# Gero_Board.net
KiCad netlist of a schematic drawn in Altium Designer
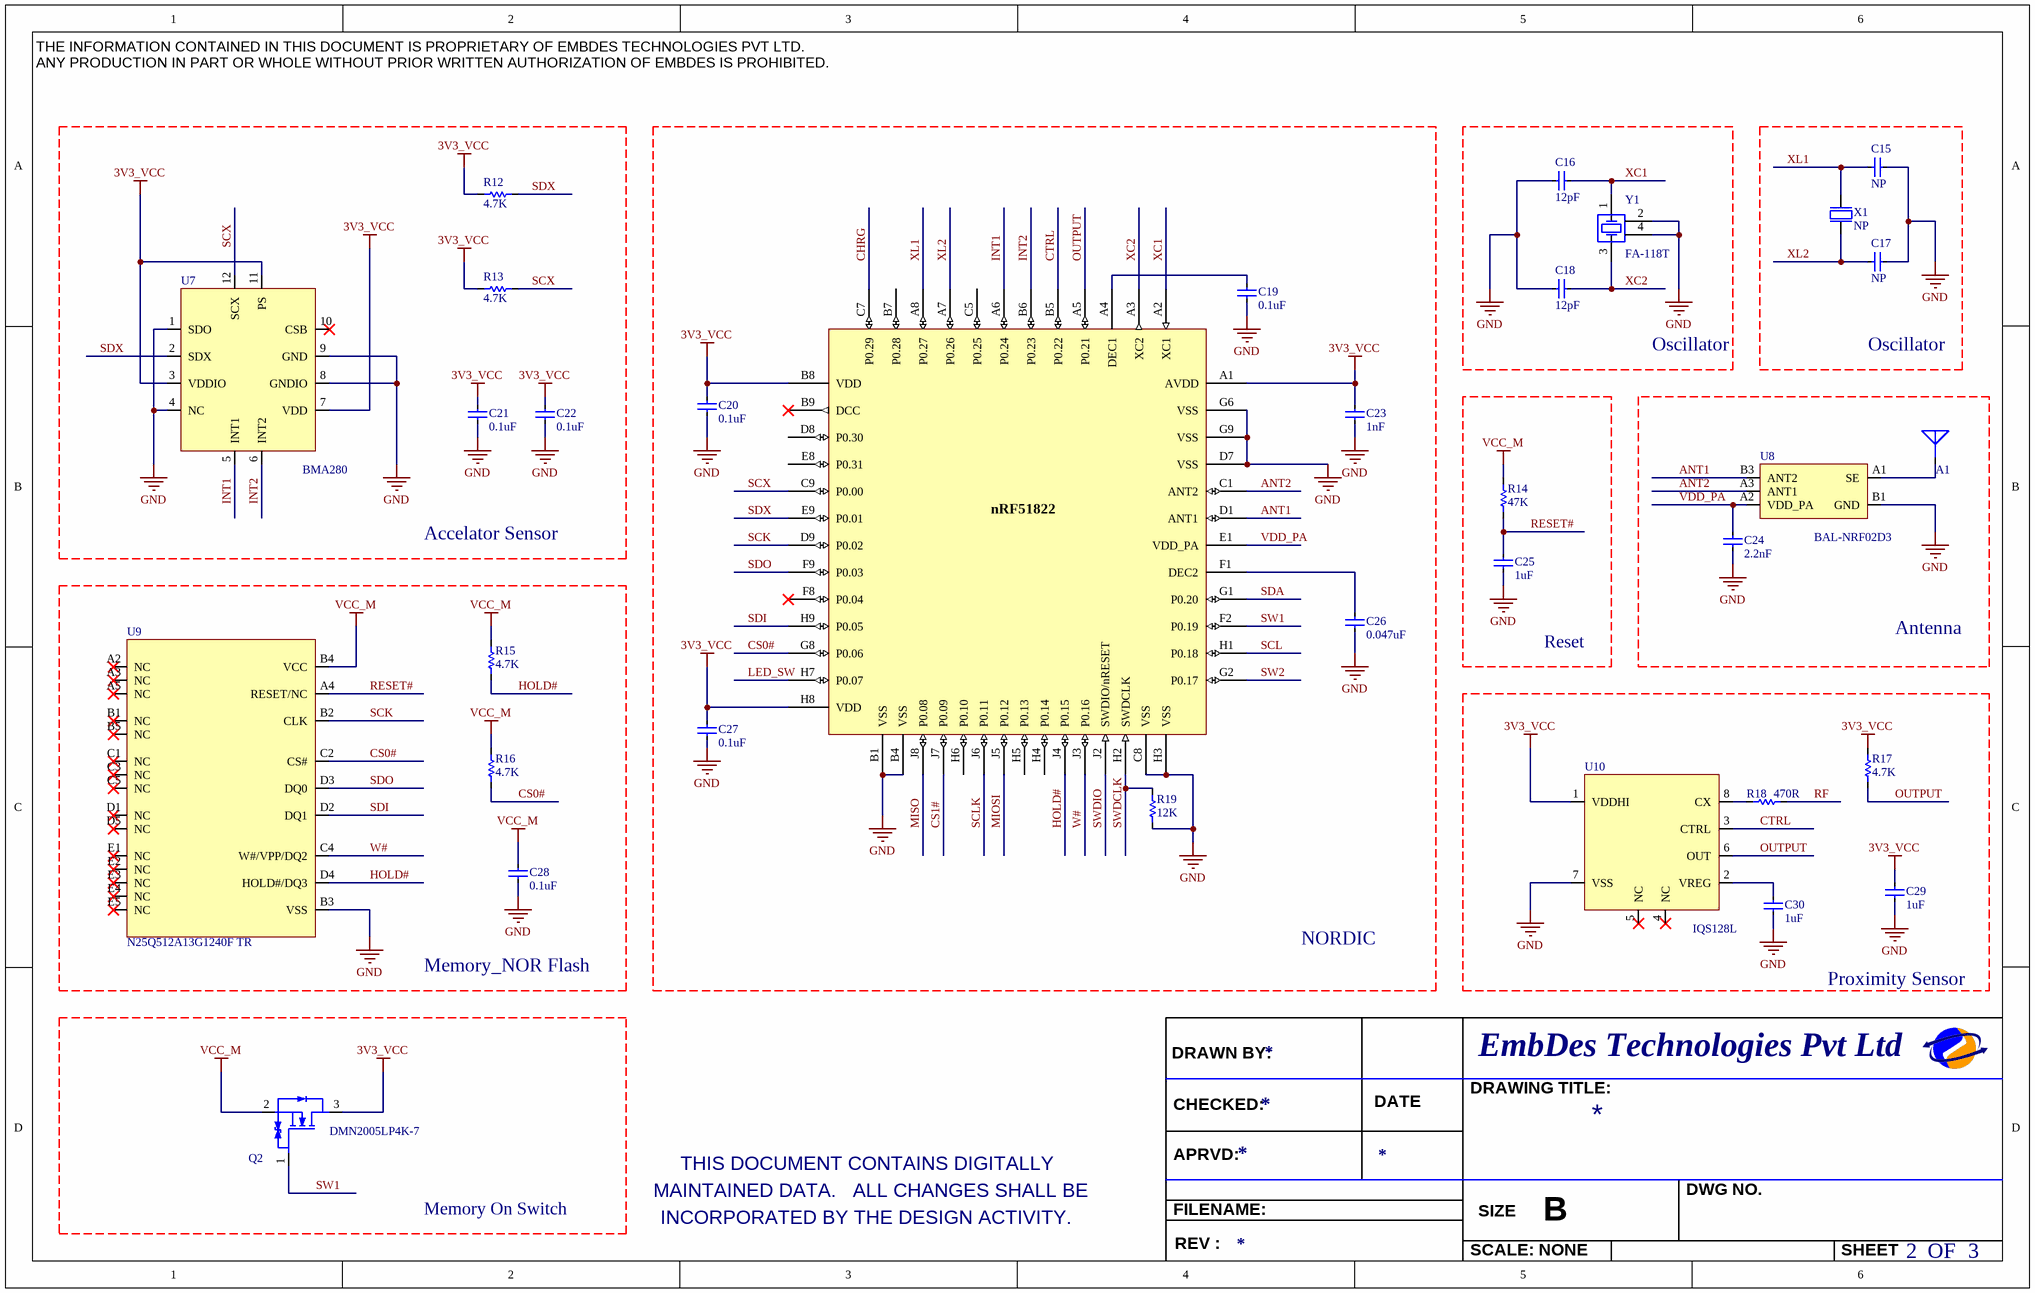
[diagram p0: Gero_Board..SchDoc]

(export (version "E")
  (design (tool "Eeschema 10.0.6"))
  (components
    (comp (ref "*1")
      (value "ol Bluetooth Low Energy and 2.4GHz proprietary system-on-chip")
      (libsource (lib "Gero_Board") (part "ol Bluetooth Low Energy and 2.4GHz proprietary system-on-chip"))
    )
    (comp (ref "A1")
      (value "DCAK0008-Dielectric Chip Antenna")
      (fields
        (field (name "MANUFACTURER") "CIROCOMM TECHNOLOGY")
        (field (name "MANUFACUTURER PART NO") "03A40D5M00J0110")
      )
      (libsource (lib "Gero_Board") (part "DCAK0008-Dielectric Chip Antenna"))
    )
    (comp (ref "C15")
      (value "NP")
      (footprint "CAPC1005X04L")
      (description "CAP CER 12PF 25V 5% NP0 0201")
      (fields
        (field (name "MANUFACTURER") "TDK Corporation")
        (field (name "MANUFACTURER PART NUMBER") "C0603C0G1E120J030BA")
      )
      (libsource (lib "Gero_Board") (part "CAP CER 12PF 25V 5% NP0 0201"))
    )
    (comp (ref "C16")
      (value "12pF")
      (footprint "CAPC1005X04L")
      (description "CAP CER 12PF 25V 5% NP0 0201")
      (fields
        (field (name "MANUFACTURER") "TDK Corporation")
        (field (name "MANUFACTURER PART NUMBER") "C0603C0G1E120J030BA")
      )
      (libsource (lib "Gero_Board") (part "CAP CER 12PF 25V 5% NP0 0201"))
    )
    (comp (ref "C17")
      (value "NP")
      (footprint "CAPC1005X04L")
      (description "CAP CER 12PF 25V 5% NP0 0201")
      (fields
        (field (name "MANUFACTURER") "TDK Corporation")
        (field (name "MANUFACTURER PART NUMBER") "C0603C0G1E120J030BA")
      )
      (libsource (lib "Gero_Board") (part "CAP CER 12PF 25V 5% NP0 0201"))
    )
    (comp (ref "C18")
      (value "12pF")
      (footprint "CAPC1005X04L")
      (description "CAP CER 12PF 25V 5% NP0 0201")
      (fields
        (field (name "MANUFACTURER") "TDK Corporation")
        (field (name "MANUFACTURER PART NUMBER") "C0603C0G1E120J030BA")
      )
      (libsource (lib "Gero_Board") (part "CAP CER 12PF 25V 5% NP0 0201"))
    )
    (comp (ref "C19")
      (value "0.1uF")
      (footprint "CAPC1005X04L")
      (description "CAP CER 0.1UF 16V 10% X5R 0201")
      (fields
        (field (name "MANUFACTURER") "TDK Corporation")
        (field (name "MANUFACTURER PART NUMBER") "C0603X5R1C104K030BC")
      )
      (libsource (lib "Gero_Board") (part "CAP CER 0.1UF 16V 10% X5R 0201"))
    )
    (comp (ref "C20")
      (value "0.1uF")
      (footprint "CAPC1005X04L")
      (description "CAP CER 0.1UF 16V 10% X5R 0201")
      (fields
        (field (name "MANUFACTURER") "TDK Corporation")
        (field (name "MANUFACTURER PART NUMBER") "C0603X5R1C104K030BC")
      )
      (libsource (lib "Gero_Board") (part "CAP CER 0.1UF 16V 10% X5R 0201"))
    )
    (comp (ref "C21")
      (value "0.1uF")
      (footprint "CAPC1005X04L")
      (description "CAP CER 0.1UF 16V 10% X5R 0201")
      (fields
        (field (name "MANUFACTURER") "TDK Corporation")
        (field (name "MANUFACTURER PART NUMBER") "C0603X5R1C104K030BC")
      )
      (libsource (lib "Gero_Board") (part "CAP CER 0.1UF 16V 10% X5R 0201"))
    )
    (comp (ref "C22")
      (value "0.1uF")
      (footprint "CAPC1005X04L")
      (description "CAP CER 0.1UF 16V 10% X5R 0201")
      (fields
        (field (name "MANUFACTURER") "TDK Corporation")
        (field (name "MANUFACTURER PART NUMBER") "C0603X5R1C104K030BC")
      )
      (libsource (lib "Gero_Board") (part "CAP CER 0.1UF 16V 10% X5R 0201"))
    )
    (comp (ref "C23")
      (value "1nF")
      (footprint "CAPC1005X04L")
      (description "CAP CER 1000PF 25V 10% X7R 0201")
      (fields
        (field (name "MANUFACTURER") "TDK Corporation")
        (field (name "MANUFACTURER PART NUMBER") "C0603X7R1E102K030BA")
      )
      (libsource (lib "Gero_Board") (part "CAP CER 1000PF 25V 10% X7R 0201"))
    )
    (comp (ref "C24")
      (value "2.2nF")
      (footprint "CAPC1005X04L")
      (description "CAP CER 2200PF 16V 10% X7R 0201")
      (fields
        (field (name "MANUFACTURER") "TDK Corporation")
        (field (name "MANUFACTURER PART NUMBER") "C0603X7R1C222K030BA")
      )
      (libsource (lib "Gero_Board") (part "CAP CER 2200PF 16V 10% X7R 0201"))
    )
    (comp (ref "C25")
      (value "1uF")
      (footprint "CAPC1005X04L")
      (description "CAP CER 1UF 16V 10% X5R 0402")
      (fields
        (field (name "MANUFACTURER") "TDK Corporation")
        (field (name "MANUFACTURER PART NUMBER") "C1005X5R1C105K050BC")
      )
      (libsource (lib "Gero_Board.~(283)") (part "CAP CER 1UF 16V 10% X5R 0402"))
    )
    (comp (ref "C26")
      (value "0.047uF")
      (footprint "CAPC1005X04L")
      (description "CAP CER 0.047UF 16V 10% X6S 0201")
      (fields
        (field (name "MANUFACTURER") "TDK Corporation")
        (field (name "MANUFACTURER PART NUMBER") "C0603X6S1C473K030BC")
      )
      (libsource (lib "Gero_Board") (part "CAP CER 0.047UF 16V 10% X6S 0201"))
    )
    (comp (ref "C27")
      (value "0.1uF")
      (footprint "CAPC1005X04L")
      (description "CAP CER 0.1UF 16V 10% X5R 0201")
      (fields
        (field (name "MANUFACTURER") "TDK Corporation")
        (field (name "MANUFACTURER PART NUMBER") "C0603X5R1C104K030BC")
      )
      (libsource (lib "Gero_Board") (part "CAP CER 0.1UF 16V 10% X5R 0201"))
    )
    (comp (ref "C28")
      (value "0.1uF")
      (footprint "CAPC1005X04L")
      (description "CAP CER 0.1UF 16V 10% X5R 0201")
      (fields
        (field (name "MANUFACTURER") "TDK Corporation")
        (field (name "MANUFACTURER PART NUMBER") "C0603X5R1C104K030BC")
      )
      (libsource (lib "Gero_Board") (part "CAP CER 0.1UF 16V 10% X5R 0201"))
    )
    (comp (ref "C29")
      (value "1uF")
      (footprint "CAPC1005X04L")
      (description "CAP CER 1UF 16V 10% X5R 0402")
      (fields
        (field (name "MANUFACTURER") "TDK Corporation")
        (field (name "MANUFACTURER PART NUMBER") "C1005X5R1C105K050BC")
      )
      (libsource (lib "Gero_Board.~(283)") (part "CAP CER 1UF 16V 10% X5R 0402"))
    )
    (comp (ref "C30")
      (value "1uF")
      (footprint "CAPC1005X04L")
      (description "CAP CER 1UF 16V 10% X5R 0402")
      (fields
        (field (name "MANUFACTURER") "TDK Corporation")
        (field (name "MANUFACTURER PART NUMBER") "C1005X5R1C105K050BC")
      )
      (libsource (lib "Gero_Board.~(283)") (part "CAP CER 1UF 16V 10% X5R 0402"))
    )
    (comp (ref "Q2")
      (value "MOSFET N-CH 20V 200MA 3-DFN")
      (fields (field (name "MANUFACTURER") "Diodes Inc") (field (name "MFG PART NO") "DMN2005LP4K-7"))
      (libsource (lib "Gero_Board.~(283)") (part "MOSFET N-CH 20V 200MA 3-DFN"))
    )
    (comp (ref "R12")
      (value "4.7K")
      (footprint "R0402")
      (description "RES 4.7K OHM 1/20W 1% 0201 SMD")
      (fields (field (name "MANUFACTURER") "Panasonic Electronic Components"))
      (libsource (lib "Gero_Board") (part "RES 4.7K OHM 1/20W 1% 0201 SMD"))
    )
    (comp (ref "R13")
      (value "4.7K")
      (footprint "R0402")
      (description "RES 4.7K OHM 1/20W 1% 0201 SMD")
      (fields (field (name "MANUFACTURER") "Panasonic Electronic Components"))
      (libsource (lib "Gero_Board") (part "RES 4.7K OHM 1/20W 1% 0201 SMD"))
    )
    (comp (ref "R14")
      (value "47K")
      (footprint "R0402")
      (description "RES 47K OHM 1/20W 1% 0201 SMD")
      (fields (field (name "MANUFACTURER") "Panasonic Electronic Components"))
      (libsource (lib "Gero_Board") (part "RES 47K OHM 1/20W 1% 0201 SMD"))
    )
    (comp (ref "R15")
      (value "4.7K")
      (footprint "R0402")
      (description "RES 4.7K OHM 1/20W 1% 0201 SMD")
      (fields (field (name "MANUFACTURER") "Panasonic Electronic Components"))
      (libsource (lib "Gero_Board") (part "RES 4.7K OHM 1/20W 1% 0201 SMD"))
    )
    (comp (ref "R16")
      (value "4.7K")
      (footprint "R0402")
      (description "RES 4.7K OHM 1/20W 1% 0201 SMD")
      (fields (field (name "MANUFACTURER") "Panasonic Electronic Components"))
      (libsource (lib "Gero_Board") (part "RES 4.7K OHM 1/20W 1% 0201 SMD"))
    )
    (comp (ref "R17")
      (value "4.7K")
      (footprint "R0402")
      (description "RES 4.7K OHM 1/20W 1% 0201 SMD")
      (fields (field (name "MANUFACTURER") "Panasonic Electronic Components"))
      (libsource (lib "Gero_Board") (part "RES 4.7K OHM 1/20W 1% 0201 SMD"))
    )
    (comp (ref "R18")
      (value "470R")
      (footprint "R0402")
      (description "RES 470 OHM 1/20W 1% 0201 SMD")
      (fields (field (name "MANUFACTURER") "Panasonic Electronic Components"))
      (libsource (lib "Gero_Board") (part "RES 470 OHM 1/20W 1% 0201 SMD"))
    )
    (comp (ref "R19")
      (value "12K")
      (footprint "R0402")
      (description "RES 12K OHM 1/20W 1% 0201 SMD")
      (libsource (lib "Gero_Board") (part "RES 12K OHM 1/20W 1% 0201 SMD"))
    )
    (comp (ref "U7")
      (value "SENSOR ACCELEROMETER")
      (fields
        (field (name "MANUFACTURER") "Bosch Sensortec")
        (field (name "MANUFACTURER PART NUMBER") "BMA280")
      )
      (libsource (lib "Gero_Board.~(283)") (part "SENSOR ACCELEROMETER"))
    )
    (comp (ref "U8")
      (value "50 ohm balun transformer for 2.45GHz ISM")
      (footprint "BAL-NRF02D3")
      (fields
        (field (name "MANUFACTURER") "ST Microelectronics")
        (field (name "MANUFACTURER PART NUMBER") "BAL-NRF02D3")
      )
      (libsource (lib "Gero_Board.~(283)") (part "50 ohm balun transformer for 2.45GHz ISM"))
    )
    (comp (ref "U9")
      (value "IC FLASH 128MX4 SLC TBGA DDP")
      (footprint "N25Q512A13G1240F")
      (fields
        (field (name "MANUFACTURER") "Micron Technology Inc")
        (field (name "MANUFACTURER PART NUMBER") "N25Q512A13G1240F TR")
      )
      (libsource (lib "Gero_Board.~(283)") (part "IC FLASH 128MX4 SLC TBGA DDP"))
    )
    (comp (ref "U10")
      (value "Single Channel Capacitive Proximity/Touch Controller")
      (footprint "IQS128")
      (fields (field (name "MANUFACTURER") "Azoteq") (field (name "MANUFACTURER PART NO") "IQS128L"))
      (libsource (lib "Gero_Board.~(283)") (part "Single Channel Capacitive Proximity/Touch Controller"))
    )
    (comp (ref "X1")
      (value "NP")
      (fields (field (name "Comment") "xtal"))
      (libsource (lib "Gero_Board") (part "xtal"))
    )
    (comp (ref "Y1")
      (value "MHz Range Crystal Unit Ultra Miniature Size Low Profile SMD")
      (footprint "FA-118T")
      (fields (field (name "MANUFACTURER") "EPSON") (field (name "MANUFACTURER PART NUMBER") "FA-118T"))
      (libsource (lib "Gero_Board.~(283)") (part "MHz Range Crystal Unit Ultra Miniature Size Low Profile SMD"))
    )
  )
  (nets
    (net (code "1") (name "/ANT1") (class "Default")
      (node (ref "*1") (pin "D1") (pinfunction "ANT1_D1") (pintype "bidirectional"))
      (node (ref "U8") (pin "B3") (pinfunction "ANT2_B3") (pintype "passive"))
    )
    (net (code "2") (name "/ANT2") (class "Default")
      (node (ref "*1") (pin "C1") (pinfunction "ANT2_C1") (pintype "bidirectional"))
      (node (ref "U8") (pin "A3") (pinfunction "ANT1_A3") (pintype "passive"))
    )
    (net (code "3") (name "/CHRG") (class "Default")
      (node (ref "*1") (pin "C7") (pinfunction "P0.29_C7") (pintype "bidirectional"))
    )
    (net (code "4") (name "/CS0#") (class "Default")
      (node (ref "*1") (pin "G8") (pinfunction "P0.06_G8") (pintype "bidirectional"))
      (node (ref "R16") (pin "1") (pinfunction "1_1") (pintype "passive"))
      (node (ref "U9") (pin "C2") (pinfunction "CS#_C2") (pintype "passive"))
    )
    (net (code "5") (name "/CS1#") (class "Default")
      (node (ref "*1") (pin "J7") (pinfunction "P0.09_J7") (pintype "bidirectional"))
    )
    (net (code "6") (name "/CTRL") (class "Default")
      (node (ref "*1") (pin "B5") (pinfunction "P0.22_B5") (pintype "bidirectional"))
      (node (ref "U10") (pin "3") (pinfunction "CTRL_3") (pintype "passive"))
    )
    (net (code "7") (name "/HOLD#") (class "Default")
      (node (ref "*1") (pin "J4") (pinfunction "P0.15_J4") (pintype "bidirectional"))
      (node (ref "R15") (pin "1") (pinfunction "1_1") (pintype "passive"))
      (node (ref "U9") (pin "D4") (pinfunction "HOLD#/DQ3_D4") (pintype "passive"))
    )
    (net (code "8") (name "/INT1") (class "Default")
      (node (ref "*1") (pin "A6") (pinfunction "P0.24_A6") (pintype "bidirectional"))
      (node (ref "U7") (pin "5") (pinfunction "INT1_5") (pintype "passive"))
    )
    (net (code "9") (name "/INT2") (class "Default")
      (node (ref "*1") (pin "B6") (pinfunction "P0.23_B6") (pintype "bidirectional"))
      (node (ref "U7") (pin "6") (pinfunction "INT2_6") (pintype "passive"))
    )
    (net (code "10") (name "/LED_SW") (class "Default")
      (node (ref "*1") (pin "H7") (pinfunction "P0.07_H7") (pintype "bidirectional"))
    )
    (net (code "11") (name "/MIOSI") (class "Default")
      (node (ref "*1") (pin "J5") (pinfunction "P0.12_J5") (pintype "bidirectional"))
    )
    (net (code "12") (name "/MISO") (class "Default")
      (node (ref "*1") (pin "J8") (pinfunction "P0.08_J8") (pintype "bidirectional"))
    )
    (net (code "13") (name "/OUTPUT") (class "Default")
      (node (ref "*1") (pin "A5") (pinfunction "P0.21_A5") (pintype "bidirectional"))
      (node (ref "R17") (pin "1") (pinfunction "1_1") (pintype "passive"))
      (node (ref "U10") (pin "6") (pinfunction "OUT_6") (pintype "passive"))
    )
    (net (code "14") (name "/RESET#") (class "Default")
      (node (ref "C25") (pin "2") (pinfunction "2_2") (pintype "passive"))
      (node (ref "R14") (pin "1") (pinfunction "1_1") (pintype "passive"))
      (node (ref "U9") (pin "A4") (pinfunction "RESET/NC_A4") (pintype "passive"))
    )
    (net (code "15") (name "/RF") (class "Default")
      (node (ref "R18") (pin "2") (pinfunction "2_2") (pintype "passive"))
    )
    (net (code "16") (name "/SCK") (class "Default")
      (node (ref "*1") (pin "D9") (pinfunction "P0.02_D9") (pintype "bidirectional"))
      (node (ref "U9") (pin "B2") (pinfunction "CLK_B2") (pintype "passive"))
    )
    (net (code "17") (name "/SCL") (class "Default")
      (node (ref "*1") (pin "H1") (pinfunction "P0.18_H1") (pintype "bidirectional"))
    )
    (net (code "18") (name "/SCLK") (class "Default")
      (node (ref "*1") (pin "J6") (pinfunction "P0.11_J6") (pintype "bidirectional"))
    )
    (net (code "19") (name "/SCX") (class "Default")
      (node (ref "*1") (pin "C9") (pinfunction "P0.00_C9") (pintype "bidirectional"))
      (node (ref "R13") (pin "2") (pinfunction "2_2") (pintype "passive"))
      (node (ref "U7") (pin "12") (pinfunction "SCX_12") (pintype "passive"))
    )
    (net (code "20") (name "/SDA") (class "Default")
      (node (ref "*1") (pin "G1") (pinfunction "P0.20_G1") (pintype "bidirectional"))
    )
    (net (code "21") (name "/SDI") (class "Default")
      (node (ref "*1") (pin "H9") (pinfunction "P0.05_H9") (pintype "bidirectional"))
      (node (ref "U9") (pin "D2") (pinfunction "DQ1_D2") (pintype "passive"))
    )
    (net (code "22") (name "/SDO") (class "Default")
      (node (ref "*1") (pin "F9") (pinfunction "P0.03_F9") (pintype "bidirectional"))
      (node (ref "U9") (pin "D3") (pinfunction "DQ0_D3") (pintype "passive"))
    )
    (net (code "23") (name "/SDX") (class "Default")
      (node (ref "*1") (pin "E9") (pinfunction "P0.01_E9") (pintype "bidirectional"))
      (node (ref "R12") (pin "2") (pinfunction "2_2") (pintype "passive"))
      (node (ref "U7") (pin "2") (pinfunction "SDX_2") (pintype "passive"))
    )
    (net (code "24") (name "/SW1") (class "Default")
      (node (ref "*1") (pin "F2") (pinfunction "P0.19_F2") (pintype "bidirectional"))
      (node (ref "Q2") (pin "1") (pinfunction "G_1") (pintype "passive"))
    )
    (net (code "25") (name "/SW2") (class "Default")
      (node (ref "*1") (pin "G2") (pinfunction "P0.17_G2") (pintype "bidirectional"))
    )
    (net (code "26") (name "/SWDCLK") (class "Default")
      (node (ref "*1") (pin "H2") (pinfunction "SWDCLK_H2") (pintype "input"))
      (node (ref "R19") (pin "2") (pinfunction "2_2") (pintype "passive"))
    )
    (net (code "27") (name "/SWDIO") (class "Default")
      (node (ref "*1") (pin "J2") (pinfunction "SWDIO/nRESET_J2") (pintype "input"))
    )
    (net (code "28") (name "/VDD_PA") (class "Default")
      (node (ref "*1") (pin "E1") (pinfunction "VDD_PA_E1") (pintype "power_in"))
      (node (ref "C24") (pin "2") (pinfunction "2_2") (pintype "passive"))
      (node (ref "U8") (pin "A2") (pinfunction "VDD_PA_A2") (pintype "passive"))
    )
    (net (code "29") (name "/W#") (class "Default")
      (node (ref "*1") (pin "J3") (pinfunction "P0.16_J3") (pintype "bidirectional"))
      (node (ref "U9") (pin "C4") (pinfunction "W#/VPP/DQ2_C4") (pintype "passive"))
    )
    (net (code "30") (name "/XC1") (class "Default")
      (node (ref "*1") (pin "A2") (pinfunction "XC1_A2") (pintype "input"))
      (node (ref "C16") (pin "2") (pinfunction "2_2") (pintype "passive"))
      (node (ref "Y1") (pin "1") (pinfunction "XTAL_IN_1") (pintype "passive"))
    )
    (net (code "31") (name "/XC2") (class "Default")
      (node (ref "*1") (pin "A3") (pinfunction "XC2_A3") (pintype "output"))
      (node (ref "C18") (pin "2") (pinfunction "2_2") (pintype "passive"))
      (node (ref "Y1") (pin "3") (pinfunction "XTAL_OUT_3") (pintype "passive"))
    )
    (net (code "32") (name "/XL1") (class "Default")
      (node (ref "*1") (pin "A8") (pinfunction "P0.27_A8") (pintype "bidirectional"))
      (node (ref "C15") (pin "1") (pinfunction "1_1") (pintype "passive"))
      (node (ref "X1") (pin "1") (pinfunction "inp_1") (pintype "passive"))
    )
    (net (code "33") (name "/XL2") (class "Default")
      (node (ref "*1") (pin "A7") (pinfunction "P0.26_A7") (pintype "bidirectional"))
      (node (ref "C17") (pin "1") (pinfunction "1_1") (pintype "passive"))
      (node (ref "X1") (pin "3") (pinfunction "out_3") (pintype "passive"))
    )
    (net (code "34") (name "3V3_VCC") (class "Default")
      (node (ref "*1") (pin "A1") (pinfunction "AVDD_A1") (pintype "power_in"))
      (node (ref "*1") (pin "B8") (pinfunction "VDD_B8") (pintype "power_in"))
      (node (ref "*1") (pin "H8") (pinfunction "VDD_H8") (pintype "power_in"))
      (node (ref "C20") (pin "2") (pinfunction "2_2") (pintype "passive"))
      (node (ref "C21") (pin "2") (pinfunction "2_2") (pintype "passive"))
      (node (ref "C22") (pin "2") (pinfunction "2_2") (pintype "passive"))
      (node (ref "C23") (pin "2") (pinfunction "2_2") (pintype "passive"))
      (node (ref "C27") (pin "2") (pinfunction "2_2") (pintype "passive"))
      (node (ref "C29") (pin "2") (pinfunction "2_2") (pintype "passive"))
      (node (ref "Q2") (pin "3") (pinfunction "D_3") (pintype "passive"))
      (node (ref "R12") (pin "1") (pinfunction "1_1") (pintype "passive"))
      (node (ref "R13") (pin "1") (pinfunction "1_1") (pintype "passive"))
      (node (ref "R17") (pin "2") (pinfunction "2_2") (pintype "passive"))
      (node (ref "U10") (pin "1") (pinfunction "VDDHI_1") (pintype "passive"))
      (node (ref "U7") (pin "11") (pinfunction "PS_11") (pintype "passive"))
      (node (ref "U7") (pin "3") (pinfunction "VDDIO_3") (pintype "passive"))
      (node (ref "U7") (pin "7") (pinfunction "VDD_7") (pintype "passive"))
    )
    (net (code "35") (name "GND") (class "Default")
      (node (ref "*1") (pin "B1") (pinfunction "VSS_B1") (pintype "power_in"))
      (node (ref "*1") (pin "B4") (pinfunction "VSS_B4") (pintype "power_in"))
      (node (ref "*1") (pin "C8") (pinfunction "VSS_C8") (pintype "power_in"))
      (node (ref "*1") (pin "D7") (pinfunction "VSS_D7") (pintype "power_in"))
      (node (ref "*1") (pin "G6") (pinfunction "VSS_G6") (pintype "power_in"))
      (node (ref "*1") (pin "G9") (pinfunction "VSS_G9") (pintype "power_in"))
      (node (ref "*1") (pin "H3") (pinfunction "VSS_H3") (pintype "power_in"))
      (node (ref "C15") (pin "2") (pinfunction "2_2") (pintype "passive"))
      (node (ref "C16") (pin "1") (pinfunction "1_1") (pintype "passive"))
      (node (ref "C17") (pin "2") (pinfunction "2_2") (pintype "passive"))
      (node (ref "C18") (pin "1") (pinfunction "1_1") (pintype "passive"))
      (node (ref "C19") (pin "1") (pinfunction "1_1") (pintype "passive"))
      (node (ref "C20") (pin "1") (pinfunction "1_1") (pintype "passive"))
      (node (ref "C21") (pin "1") (pinfunction "1_1") (pintype "passive"))
      (node (ref "C22") (pin "1") (pinfunction "1_1") (pintype "passive"))
      (node (ref "C23") (pin "1") (pinfunction "1_1") (pintype "passive"))
      (node (ref "C24") (pin "1") (pinfunction "1_1") (pintype "passive"))
      (node (ref "C25") (pin "1") (pinfunction "1_1") (pintype "passive"))
      (node (ref "C26") (pin "1") (pinfunction "1_1") (pintype "passive"))
      (node (ref "C27") (pin "1") (pinfunction "1_1") (pintype "passive"))
      (node (ref "C28") (pin "1") (pinfunction "1_1") (pintype "passive"))
      (node (ref "C29") (pin "1") (pinfunction "1_1") (pintype "passive"))
      (node (ref "C30") (pin "1") (pinfunction "1_1") (pintype "passive"))
      (node (ref "R19") (pin "1") (pinfunction "1_1") (pintype "passive"))
      (node (ref "U10") (pin "7") (pinfunction "VSS_7") (pintype "passive"))
      (node (ref "U7") (pin "1") (pinfunction "SDO_1") (pintype "passive"))
      (node (ref "U7") (pin "4") (pinfunction "NC_4") (pintype "passive"))
      (node (ref "U7") (pin "8") (pinfunction "GNDIO_8") (pintype "passive"))
      (node (ref "U7") (pin "9") (pinfunction "GND_9") (pintype "passive"))
      (node (ref "U8") (pin "B1") (pinfunction "GND_B1") (pintype "passive"))
      (node (ref "U9") (pin "B3") (pinfunction "VSS_B3") (pintype "passive"))
      (node (ref "Y1") (pin "2") (pinfunction "GND_2") (pintype "passive"))
      (node (ref "Y1") (pin "4") (pinfunction "GND_4") (pintype "passive"))
    )
    (net (code "36") (name "Net-(*1-DEC1)") (class "Default")
      (node (ref "*1") (pin "A4") (pinfunction "DEC1_A4") (pintype "power_in"))
      (node (ref "C19") (pin "2") (pinfunction "2_2") (pintype "passive"))
    )
    (net (code "37") (name "Net-(*1-DEC2)") (class "Default")
      (node (ref "*1") (pin "F1") (pinfunction "DEC2_F1") (pintype "power_in"))
      (node (ref "C26") (pin "2") (pinfunction "2_2") (pintype "passive"))
    )
    (net (code "38") (name "Net-(U10-CX)") (class "Default")
      (node (ref "R18") (pin "1") (pinfunction "1_1") (pintype "passive"))
      (node (ref "U10") (pin "8") (pinfunction "CX_8") (pintype "passive"))
    )
    (net (code "39") (name "Net-(U10-VREG)") (class "Default")
      (node (ref "C30") (pin "2") (pinfunction "2_2") (pintype "passive"))
      (node (ref "U10") (pin "2") (pinfunction "VREG_2") (pintype "passive"))
    )
    (net (code "40") (name "VCC_M") (class "Default")
      (node (ref "C28") (pin "2") (pinfunction "2_2") (pintype "passive"))
      (node (ref "Q2") (pin "2") (pinfunction "S_2") (pintype "passive"))
      (node (ref "R14") (pin "2") (pinfunction "2_2") (pintype "passive"))
      (node (ref "R15") (pin "2") (pinfunction "2_2") (pintype "passive"))
      (node (ref "R16") (pin "2") (pinfunction "2_2") (pintype "passive"))
      (node (ref "U9") (pin "B4") (pinfunction "VCC_B4") (pintype "passive"))
    )
    (net (code "41") (name "unconnected-(*1-DCC-PadB9)") (class "Default")
      (node (ref "*1") (pin "B9") (pinfunction "DCC_B9") (pintype "output+no_connect"))
    )
    (net (code "42") (name "unconnected-(*1-P0.04-PadF8)") (class "Default")
      (node (ref "*1") (pin "F8") (pinfunction "P0.04_F8") (pintype "bidirectional+no_connect"))
    )
    (net (code "43") (name "unconnected-(*1-P0.10-PadH6)") (class "Default")
      (node (ref "*1") (pin "H6") (pinfunction "P0.10_H6") (pintype "bidirectional"))
    )
    (net (code "44") (name "unconnected-(*1-P0.13-PadH5)") (class "Default")
      (node (ref "*1") (pin "H5") (pinfunction "P0.13_H5") (pintype "bidirectional"))
    )
    (net (code "45") (name "unconnected-(*1-P0.14-PadH4)") (class "Default")
      (node (ref "*1") (pin "H4") (pinfunction "P0.14_H4") (pintype "bidirectional"))
    )
    (net (code "46") (name "unconnected-(*1-P0.25-PadC5)") (class "Default")
      (node (ref "*1") (pin "C5") (pinfunction "P0.25_C5") (pintype "bidirectional"))
    )
    (net (code "47") (name "unconnected-(*1-P0.28-PadB7)") (class "Default")
      (node (ref "*1") (pin "B7") (pinfunction "P0.28_B7") (pintype "bidirectional"))
    )
    (net (code "48") (name "unconnected-(*1-P0.30-PadD8)") (class "Default")
      (node (ref "*1") (pin "D8") (pinfunction "P0.30_D8") (pintype "bidirectional"))
    )
    (net (code "49") (name "unconnected-(*1-P0.31-PadE8)") (class "Default")
      (node (ref "*1") (pin "E8") (pinfunction "P0.31_E8") (pintype "bidirectional"))
    )
    (net (code "50") (name "unconnected-(A1-A-Pad1)") (class "Default")
      (node (ref "A1") (pin "1") (pinfunction "A_1") (pintype "passive"))
    )
    (net (code "51") (name "unconnected-(U7-CSB-Pad10)") (class "Default")
      (node (ref "U7") (pin "10") (pinfunction "CSB_10") (pintype "passive+no_connect"))
    )
    (net (code "52") (name "unconnected-(U8-SE-PadA1)") (class "Default")
      (node (ref "U8") (pin "A1") (pinfunction "SE_A1") (pintype "passive"))
    )
    (net (code "53") (name "unconnected-(U9-NC-PadA2)") (class "Default")
      (node (ref "U9") (pin "A2") (pinfunction "NC_A2") (pintype "passive+no_connect"))
    )
    (net (code "54") (name "unconnected-(U9-NC-PadA3)") (class "Default")
      (node (ref "U9") (pin "A3") (pinfunction "NC_A3") (pintype "passive+no_connect"))
    )
    (net (code "55") (name "unconnected-(U9-NC-PadA5)") (class "Default")
      (node (ref "U9") (pin "A5") (pinfunction "NC_A5") (pintype "passive+no_connect"))
    )
    (net (code "56") (name "unconnected-(U9-NC-PadB1)") (class "Default")
      (node (ref "U9") (pin "B1") (pinfunction "NC_B1") (pintype "passive+no_connect"))
    )
    (net (code "57") (name "unconnected-(U9-NC-PadB5)") (class "Default")
      (node (ref "U9") (pin "B5") (pinfunction "NC_B5") (pintype "passive+no_connect"))
    )
    (net (code "58") (name "unconnected-(U9-NC-PadC1)") (class "Default")
      (node (ref "U9") (pin "C1") (pinfunction "NC_C1") (pintype "passive+no_connect"))
    )
    (net (code "59") (name "unconnected-(U9-NC-PadC3)") (class "Default")
      (node (ref "U9") (pin "C3") (pinfunction "NC_C3") (pintype "passive+no_connect"))
    )
    (net (code "60") (name "unconnected-(U9-NC-PadC5)") (class "Default")
      (node (ref "U9") (pin "C5") (pinfunction "NC_C5") (pintype "passive+no_connect"))
    )
    (net (code "61") (name "unconnected-(U9-NC-PadD1)") (class "Default")
      (node (ref "U9") (pin "D1") (pinfunction "NC_D1") (pintype "passive+no_connect"))
    )
    (net (code "62") (name "unconnected-(U9-NC-PadD5)") (class "Default")
      (node (ref "U9") (pin "D5") (pinfunction "NC_D5") (pintype "passive+no_connect"))
    )
    (net (code "63") (name "unconnected-(U9-NC-PadE1)") (class "Default")
      (node (ref "U9") (pin "E1") (pinfunction "NC_E1") (pintype "passive+no_connect"))
    )
    (net (code "64") (name "unconnected-(U9-NC-PadE2)") (class "Default")
      (node (ref "U9") (pin "E2") (pinfunction "NC_E2") (pintype "passive+no_connect"))
    )
    (net (code "65") (name "unconnected-(U9-NC-PadE3)") (class "Default")
      (node (ref "U9") (pin "E3") (pinfunction "NC_E3") (pintype "passive+no_connect"))
    )
    (net (code "66") (name "unconnected-(U9-NC-PadE4)") (class "Default")
      (node (ref "U9") (pin "E4") (pinfunction "NC_E4") (pintype "passive+no_connect"))
    )
    (net (code "67") (name "unconnected-(U9-NC-PadE5)") (class "Default")
      (node (ref "U9") (pin "E5") (pinfunction "NC_E5") (pintype "passive+no_connect"))
    )
    (net (code "68") (name "unconnected-(U10-NC-Pad4)") (class "Default")
      (node (ref "U10") (pin "4") (pinfunction "NC_4") (pintype "passive+no_connect"))
    )
    (net (code "69") (name "unconnected-(U10-NC-Pad5)") (class "Default")
      (node (ref "U10") (pin "5") (pinfunction "NC_5") (pintype "passive+no_connect"))
    )
  )
)
